# encode_and_decode_1.net
KiCad netlist of a schematic drawn in Altium Designer
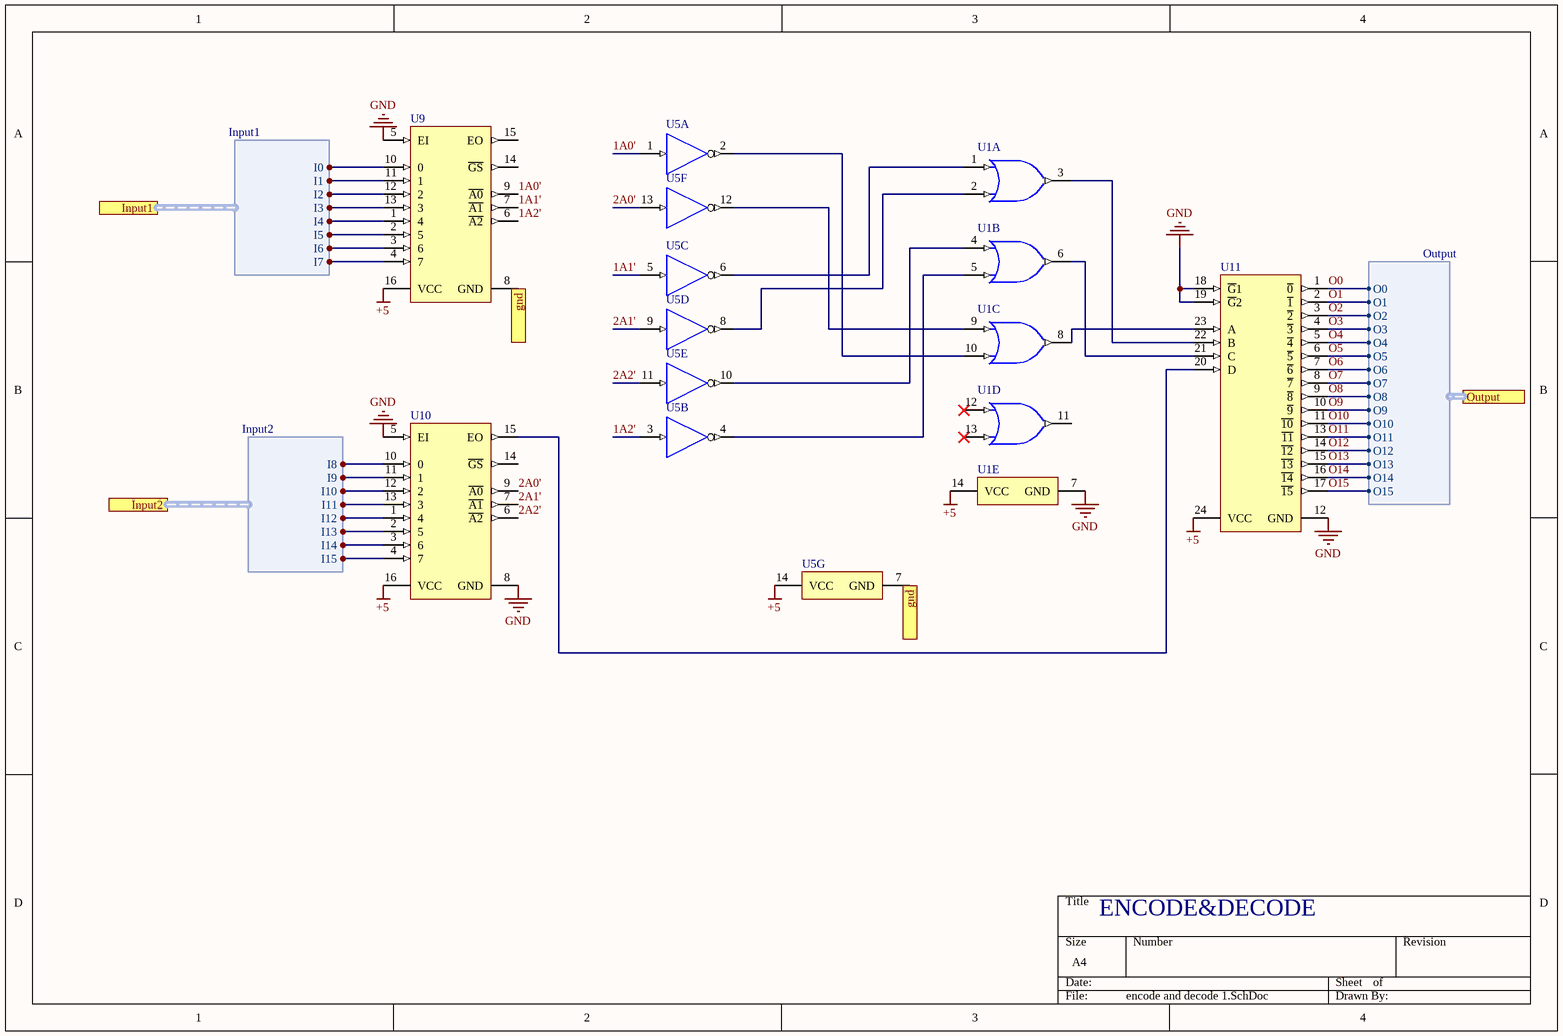
[diagram p0: encode and decode 1.SchDoc]

(export (version "E")
  (design (tool "Eeschema 10.0.6"))
  (components
    (comp (ref "U1")
      (value "SN7432N")
      (footprint "N0014A")
      (description "Quad 2-input positive-OR gates, N0014A, TUBE")
      (fields (field (name "MANUFACTURER") "Texas Instruments") (field (name "GENERIC PART NUMBER") "SN7432"))
      (libsource (lib "Altium Content Vault") (part "TI-OR-4-2IN-14"))
    )
    (comp (ref "U5")
      (value "SN74HCU04N")
      (footprint "N0014A")
      (description "Hex Inverters, N0014A, TUBE")
      (fields
        (field (name "MANUFACTURER") "Texas Instruments")
        (field (name "GENERIC PART NUMBER") "SN74HCU04")
      )
      (libsource (lib "Altium Content Vault") (part "TI-CD_SNX4XXXXXX4X_19A-14"))
    )
    (comp (ref "U9")
      (value "SN74LS148N")
      (footprint "N0016A")
      (description "8-line to 3-line priority encoder, N0016A, TUBE")
      (fields
        (field (name "GENERIC PART NUMBER") "SN74LS148")
        (field (name "MANUFACTURER") "Texas Instruments")
      )
      (libsource (lib "Altium Content Vault") (part "TI-SNX4XX148-16"))
    )
    (comp (ref "U10")
      (value "SN74LS148N")
      (footprint "N0016A")
      (description "8-line to 3-line priority encoder, N0016A, TUBE")
      (fields
        (field (name "GENERIC PART NUMBER") "SN74LS148")
        (field (name "MANUFACTURER") "Texas Instruments")
      )
      (libsource (lib "Altium Content Vault") (part "TI-SNX4XX148-16"))
    )
    (comp (ref "U11")
      (value "SN74154N")
      (footprint "N0024A")
      (description "4-Line To 16-Line Decoders/Demultiplexers, N0024A, TUBE")
      (fields
        (field (name "GENERIC PART NUMBER") "SN74154")
        (field (name "MANUFACTURER") "Texas Instruments")
      )
      (libsource (lib "Altium Content Vault") (part "TI-SN54_74154-24"))
    )
  )
  (nets
    (net (code "4") (name "+5") (class "Default")
      (node (ref "U1") (pin "14") (pinfunction "VCC_14") (pintype "power_in"))
      (node (ref "U10") (pin "16") (pinfunction "VCC_16") (pintype "power_in"))
      (node (ref "U11") (pin "24") (pinfunction "VCC_24") (pintype "power_in"))
      (node (ref "U5") (pin "14") (pinfunction "VCC_14") (pintype "power_in"))
      (node (ref "U9") (pin "16") (pinfunction "VCC_16") (pintype "power_in"))
    )
    (net (code "5") (name "/1A0'") (class "Default")
      (node (ref "U5") (pin "1") (pinfunction "1A_1") (pintype "input"))
      (node (ref "U9") (pin "9") (pinfunction "~{A0}_9") (pintype "output"))
    )
    (net (code "6") (name "/1A1'") (class "Default")
      (node (ref "U5") (pin "5") (pinfunction "3A_5") (pintype "input"))
      (node (ref "U9") (pin "7") (pinfunction "~{A1}_7") (pintype "output"))
    )
    (net (code "7") (name "/1A2'") (class "Default")
      (node (ref "U5") (pin "3") (pinfunction "2A_3") (pintype "input"))
      (node (ref "U9") (pin "6") (pinfunction "~{A2}_6") (pintype "output"))
    )
    (net (code "8") (name "/2A0'") (class "Default")
      (node (ref "U10") (pin "9") (pinfunction "~{A0}_9") (pintype "output"))
      (node (ref "U5") (pin "13") (pinfunction "6A_13") (pintype "input"))
    )
    (net (code "9") (name "/2A1'") (class "Default")
      (node (ref "U10") (pin "7") (pinfunction "~{A1}_7") (pintype "output"))
      (node (ref "U5") (pin "9") (pinfunction "4A_9") (pintype "input"))
    )
    (net (code "10") (name "/2A2'") (class "Default")
      (node (ref "U10") (pin "6") (pinfunction "~{A2}_6") (pintype "output"))
      (node (ref "U5") (pin "11") (pinfunction "5A_11") (pintype "input"))
    )
    (net (code "11") (name "/I0") (class "Default")
      (node (ref "U9") (pin "10") (pinfunction "0_10") (pintype "input"))
    )
    (net (code "12") (name "/I1") (class "Default")
      (node (ref "U9") (pin "11") (pinfunction "1_11") (pintype "input"))
    )
    (net (code "13") (name "/I2") (class "Default")
      (node (ref "U9") (pin "12") (pinfunction "2_12") (pintype "input"))
    )
    (net (code "14") (name "/I3") (class "Default")
      (node (ref "U9") (pin "13") (pinfunction "3_13") (pintype "input"))
    )
    (net (code "15") (name "/I4") (class "Default")
      (node (ref "U9") (pin "1") (pinfunction "4_1") (pintype "input"))
    )
    (net (code "16") (name "/I5") (class "Default")
      (node (ref "U9") (pin "2") (pinfunction "5_2") (pintype "input"))
    )
    (net (code "17") (name "/I6") (class "Default")
      (node (ref "U9") (pin "3") (pinfunction "6_3") (pintype "input"))
    )
    (net (code "18") (name "/I7") (class "Default")
      (node (ref "U9") (pin "4") (pinfunction "7_4") (pintype "input"))
    )
    (net (code "19") (name "/I8") (class "Default")
      (node (ref "U10") (pin "10") (pinfunction "0_10") (pintype "input"))
    )
    (net (code "20") (name "/I9") (class "Default")
      (node (ref "U10") (pin "11") (pinfunction "1_11") (pintype "input"))
    )
    (net (code "21") (name "/I10") (class "Default")
      (node (ref "U10") (pin "12") (pinfunction "2_12") (pintype "input"))
    )
    (net (code "22") (name "/I11") (class "Default")
      (node (ref "U10") (pin "13") (pinfunction "3_13") (pintype "input"))
    )
    (net (code "23") (name "/I12") (class "Default")
      (node (ref "U10") (pin "1") (pinfunction "4_1") (pintype "input"))
    )
    (net (code "24") (name "/I13") (class "Default")
      (node (ref "U10") (pin "2") (pinfunction "5_2") (pintype "input"))
    )
    (net (code "25") (name "/I14") (class "Default")
      (node (ref "U10") (pin "3") (pinfunction "6_3") (pintype "input"))
    )
    (net (code "26") (name "/I15") (class "Default")
      (node (ref "U10") (pin "4") (pinfunction "7_4") (pintype "input"))
    )
    (net (code "27") (name "/O0") (class "Default")
      (node (ref "U11") (pin "1") (pinfunction "~{0}_1") (pintype "output"))
    )
    (net (code "28") (name "/O1") (class "Default")
      (node (ref "U11") (pin "2") (pinfunction "~{1}_2") (pintype "output"))
    )
    (net (code "29") (name "/O2") (class "Default")
      (node (ref "U11") (pin "3") (pinfunction "~{2}_3") (pintype "output"))
    )
    (net (code "30") (name "/O3") (class "Default")
      (node (ref "U11") (pin "4") (pinfunction "~{3}_4") (pintype "output"))
    )
    (net (code "31") (name "/O4") (class "Default")
      (node (ref "U11") (pin "5") (pinfunction "~{4}_5") (pintype "output"))
    )
    (net (code "32") (name "/O5") (class "Default")
      (node (ref "U11") (pin "6") (pinfunction "~{5}_6") (pintype "output"))
    )
    (net (code "33") (name "/O6") (class "Default")
      (node (ref "U11") (pin "7") (pinfunction "~{6}_7") (pintype "output"))
    )
    (net (code "34") (name "/O7") (class "Default")
      (node (ref "U11") (pin "8") (pinfunction "~{7}_8") (pintype "output"))
    )
    (net (code "35") (name "/O8") (class "Default")
      (node (ref "U11") (pin "9") (pinfunction "~{8}_9") (pintype "output"))
    )
    (net (code "36") (name "/O9") (class "Default")
      (node (ref "U11") (pin "10") (pinfunction "~{9}_10") (pintype "output"))
    )
    (net (code "37") (name "/O10") (class "Default")
      (node (ref "U11") (pin "11") (pinfunction "~{10}_11") (pintype "output"))
    )
    (net (code "38") (name "/O11") (class "Default")
      (node (ref "U11") (pin "13") (pinfunction "~{11}_13") (pintype "output"))
    )
    (net (code "39") (name "/O12") (class "Default")
      (node (ref "U11") (pin "14") (pinfunction "~{12}_14") (pintype "output"))
    )
    (net (code "40") (name "/O13") (class "Default")
      (node (ref "U11") (pin "15") (pinfunction "~{13}_15") (pintype "output"))
    )
    (net (code "41") (name "/O14") (class "Default")
      (node (ref "U11") (pin "16") (pinfunction "~{14}_16") (pintype "output"))
    )
    (net (code "42") (name "/O15") (class "Default")
      (node (ref "U11") (pin "17") (pinfunction "~{15}_17") (pintype "output"))
    )
    (net (code "43") (name "/gnd") (class "Default")
      (node (ref "U5") (pin "7") (pinfunction "GND_7") (pintype "power_in"))
      (node (ref "U9") (pin "8") (pinfunction "GND_8") (pintype "power_in"))
    )
    (net (code "47") (name "GND") (class "Default")
      (node (ref "U1") (pin "7") (pinfunction "GND_7") (pintype "power_in"))
      (node (ref "U10") (pin "5") (pinfunction "EI_5") (pintype "input"))
      (node (ref "U10") (pin "8") (pinfunction "GND_8") (pintype "power_in"))
      (node (ref "U11") (pin "12") (pinfunction "GND_12") (pintype "power_in"))
      (node (ref "U11") (pin "18") (pinfunction "~{G}1_18") (pintype "input"))
      (node (ref "U11") (pin "19") (pinfunction "~{G}2_19") (pintype "input"))
      (node (ref "U9") (pin "5") (pinfunction "EI_5") (pintype "input"))
    )
    (net (code "48") (name "Net-(U1A-1A)") (class "Default")
      (node (ref "U1") (pin "1") (pinfunction "1A_1") (pintype "input"))
      (node (ref "U5") (pin "6") (pinfunction "~{3Y}_6") (pintype "output"))
    )
    (net (code "49") (name "Net-(U1A-1B)") (class "Default")
      (node (ref "U1") (pin "2") (pinfunction "1B_2") (pintype "input"))
      (node (ref "U5") (pin "8") (pinfunction "~{4Y}_8") (pintype "output"))
    )
    (net (code "50") (name "Net-(U1B-2A)") (class "Default")
      (node (ref "U1") (pin "4") (pinfunction "2A_4") (pintype "input"))
      (node (ref "U5") (pin "10") (pinfunction "~{5Y}_10") (pintype "output"))
    )
    (net (code "51") (name "Net-(U1B-2B)") (class "Default")
      (node (ref "U1") (pin "5") (pinfunction "2B_5") (pintype "input"))
      (node (ref "U5") (pin "4") (pinfunction "~{2Y}_4") (pintype "output"))
    )
    (net (code "52") (name "Net-(U1C-3A)") (class "Default")
      (node (ref "U1") (pin "9") (pinfunction "3A_9") (pintype "input"))
      (node (ref "U5") (pin "12") (pinfunction "~{6Y}_12") (pintype "output"))
    )
    (net (code "53") (name "Net-(U1C-3B)") (class "Default")
      (node (ref "U1") (pin "10") (pinfunction "3B_10") (pintype "input"))
      (node (ref "U5") (pin "2") (pinfunction "~{1Y}_2") (pintype "output"))
    )
    (net (code "54") (name "Net-(U10-EO)") (class "Default")
      (node (ref "U10") (pin "15") (pinfunction "EO_15") (pintype "output"))
      (node (ref "U11") (pin "20") (pinfunction "D_20") (pintype "input"))
    )
    (net (code "55") (name "Net-(U11-A)") (class "Default")
      (node (ref "U1") (pin "8") (pinfunction "3Y_8") (pintype "output"))
      (node (ref "U11") (pin "23") (pinfunction "A_23") (pintype "input"))
    )
    (net (code "56") (name "Net-(U11-B)") (class "Default")
      (node (ref "U1") (pin "3") (pinfunction "1Y_3") (pintype "output"))
      (node (ref "U11") (pin "22") (pinfunction "B_22") (pintype "input"))
    )
    (net (code "57") (name "Net-(U11-C)") (class "Default")
      (node (ref "U1") (pin "6") (pinfunction "2Y_6") (pintype "output"))
      (node (ref "U11") (pin "21") (pinfunction "C_21") (pintype "input"))
    )
    (net (code "58") (name "unconnected-(U1D-4A-Pad12)") (class "Default")
      (node (ref "U1") (pin "12") (pinfunction "4A_12") (pintype "input+no_connect"))
    )
    (net (code "59") (name "unconnected-(U1D-4B-Pad13)") (class "Default")
      (node (ref "U1") (pin "13") (pinfunction "4B_13") (pintype "input+no_connect"))
    )
    (net (code "60") (name "unconnected-(U1D-4Y-Pad11)") (class "Default")
      (node (ref "U1") (pin "11") (pinfunction "4Y_11") (pintype "output"))
    )
    (net (code "61") (name "unconnected-(U9-EO-Pad15)") (class "Default")
      (node (ref "U9") (pin "15") (pinfunction "EO_15") (pintype "output"))
    )
    (net (code "62") (name "unconnected-(U9-~{GS}-Pad14)") (class "Default")
      (node (ref "U9") (pin "14") (pinfunction "~{GS}_14") (pintype "output"))
    )
    (net (code "63") (name "unconnected-(U10-~{GS}-Pad14)") (class "Default")
      (node (ref "U10") (pin "14") (pinfunction "~{GS}_14") (pintype "output"))
    )
  )
)
